# display.net
KiCad netlist of a schematic drawn in Altium Designer
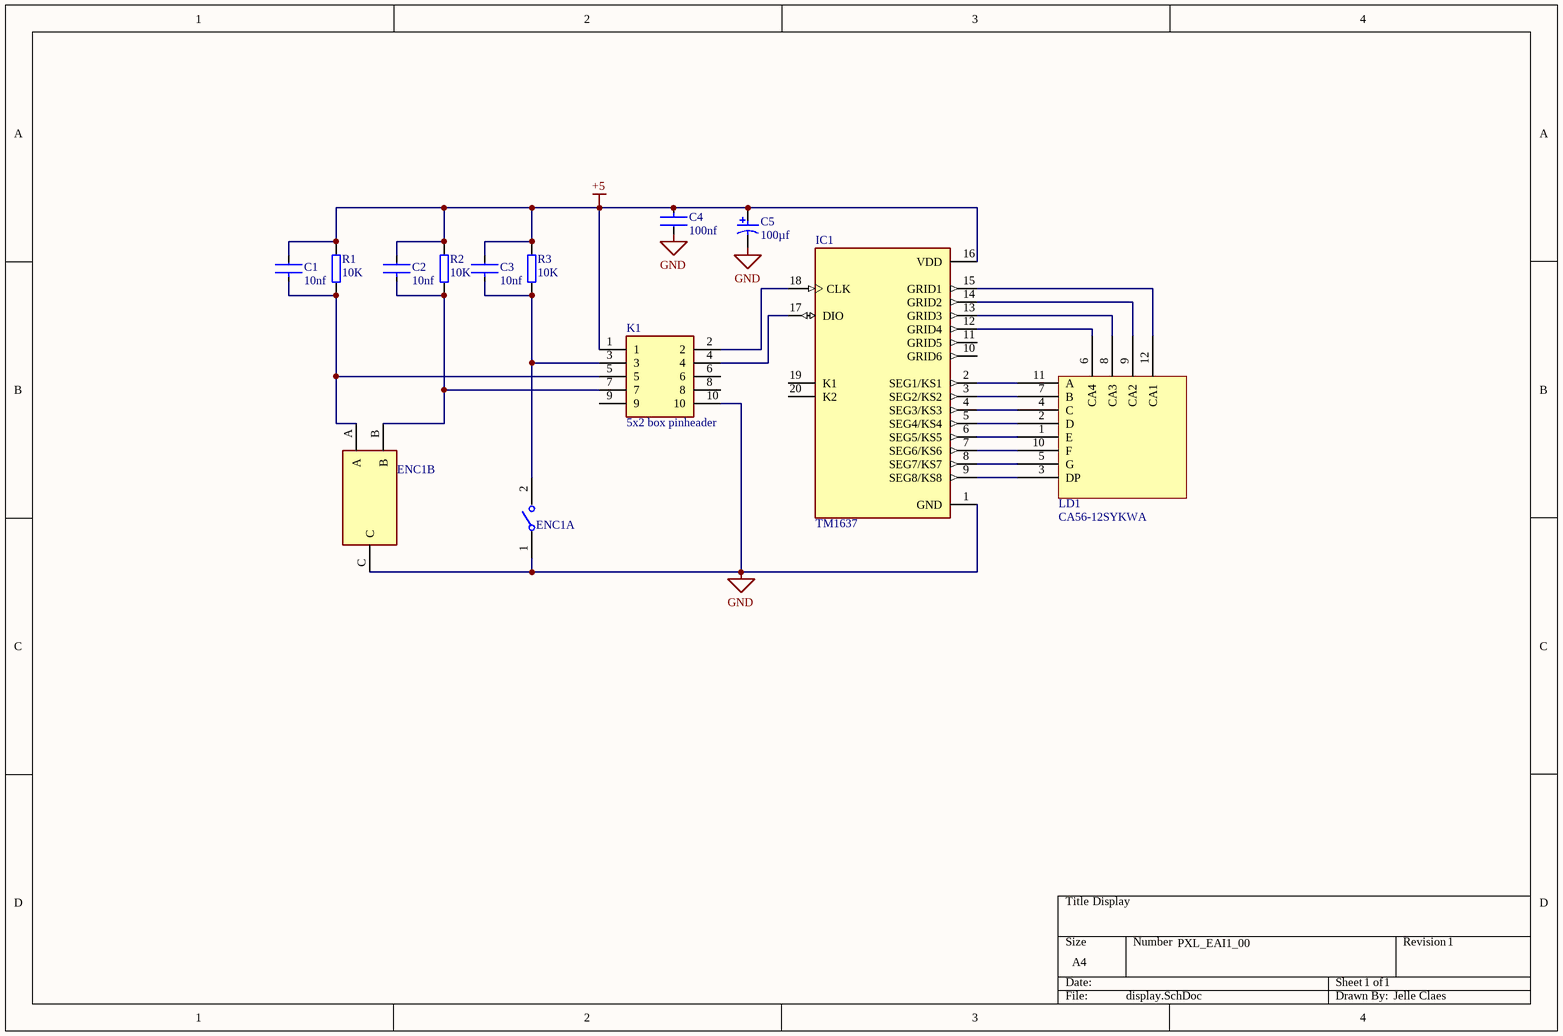
[diagram p0: display.SchDoc]

(export (version "E")
  (design (tool "Eeschema 10.0.6"))
  (components
    (comp (ref "C1")
      (value "10nf")
      (footprint "CC_0805_m")
      (fields
        (field (name "MANUFACTURER") "KEMET")
        (field (name "OCTOPART") "https://octopart.com/c0805c224k5ractu-kemet-144670")
        (field (name "MANUFACTURER PART NUMBER") "C0805C224K5RACTU")
      )
      (libsource (lib "soldeerstation") (part "Capacitor_Ceramic"))
    )
    (comp (ref "C2")
      (value "10nf")
      (footprint "CC_0805_m")
      (fields
        (field (name "MANUFACTURER") "KEMET")
        (field (name "OCTOPART") "https://octopart.com/c0805c224k5ractu-kemet-144670")
        (field (name "MANUFACTURER PART NUMBER") "C0805C224K5RACTU")
      )
      (libsource (lib "soldeerstation") (part "Capacitor_Ceramic"))
    )
    (comp (ref "C3")
      (value "10nf")
      (footprint "CC_0805_m")
      (fields
        (field (name "MANUFACTURER") "KEMET")
        (field (name "OCTOPART") "https://octopart.com/c0805c224k5ractu-kemet-144670")
        (field (name "MANUFACTURER PART NUMBER") "C0805C224K5RACTU")
      )
      (libsource (lib "soldeerstation") (part "Capacitor_Ceramic"))
    )
    (comp (ref "C4")
      (value "100nf")
      (footprint "CC_0805_m")
      (fields
        (field (name "MANUFACTURER") "KEMET")
        (field (name "OCTOPART") "https://octopart.com/c0805c224k5ractu-kemet-144670")
        (field (name "MANUFACTURER PART NUMBER") "C0805C224K5RACTU")
      )
      (libsource (lib "soldeerstation") (part "Capacitor_Ceramic"))
    )
    (comp (ref "C5")
      (value "100µf")
      (footprint "CE_D8_L10")
      (fields (field (name "MANUFACTURER") "Panasonic"))
      (libsource (lib "soldeerstation") (part "Capacitor_Electrolytic"))
    )
    (comp (ref "ENC1")
      (value "PEC11R-4220F-S0012")
      (footprint "PEC11R_4220F_S0012")
      (description "ROTARY ENCODER MECHANICAL 12PPR")
      (libsource (lib "soldeerstation") (part "PEC11R-4220F-S0012"))
    )
    (comp (ref "IC1")
      (value "TM1637")
      (footprint "SOP_20_M")
      (description "LED Drive Control Special Circuit")
      (fields (field (name "MF") "Titan Micro Electronics"))
      (libsource (lib "soldeerstation") (part "TM1637"))
    )
    (comp (ref "K1")
      (value "5x2 box pinheader")
      (footprint "2x5 box pinheader")
      (description "Connector")
      (fields (field (name "MANUFACTURER_PART_NUMBER") "T821110A1S100CEU"))
      (libsource (lib "soldeerstation") (part "5x2 box pinheader"))
    )
    (comp (ref "LD1")
      (value "CA56-12SYKWA")
      (footprint "LCD")
      (libsource (lib "soldeerstation") (part "CA56-12SYKWA"))
    )
    (comp (ref "R1")
      (value "10K")
      (footprint "R_0805_M")
      (fields (field (name "MANUFACTURER") "Vishay Dale") (field (name "PART NUMBER") "CRCW08050000Z0EA"))
      (libsource (lib "soldeerstation") (part "Resistor"))
    )
    (comp (ref "R2")
      (value "10K")
      (footprint "R_0805_M")
      (fields (field (name "MANUFACTURER") "Vishay Dale") (field (name "PART NUMBER") "CRCW08050000Z0EA"))
      (libsource (lib "soldeerstation") (part "Resistor"))
    )
    (comp (ref "R3")
      (value "10K")
      (footprint "R_0805_M")
      (fields (field (name "MANUFACTURER") "Vishay Dale") (field (name "PART NUMBER") "CRCW08050000Z0EA"))
      (libsource (lib "soldeerstation") (part "Resistor"))
    )
  )
  (nets
    (net (code "1") (name "+5") (class "Default")
      (node (ref "C1") (pin "2") (pinfunction "2_2") (pintype "passive"))
      (node (ref "C2") (pin "2") (pinfunction "2_2") (pintype "passive"))
      (node (ref "C3") (pin "2") (pinfunction "2_2") (pintype "passive"))
      (node (ref "C4") (pin "1") (pinfunction "1_1") (pintype "passive"))
      (node (ref "C5") (pin "2") (pinfunction "2_2") (pintype "passive"))
      (node (ref "IC1") (pin "16") (pinfunction "VDD_16") (pintype "power_in"))
      (node (ref "K1") (pin "1") (pinfunction "1_1") (pintype "passive"))
      (node (ref "R1") (pin "2") (pinfunction "2_2") (pintype "passive"))
      (node (ref "R2") (pin "2") (pinfunction "2_2") (pintype "passive"))
      (node (ref "R3") (pin "2") (pinfunction "2_2") (pintype "passive"))
    )
    (net (code "2") (name "GND") (class "Default")
      (node (ref "C4") (pin "2") (pinfunction "2_2") (pintype "passive"))
      (node (ref "C5") (pin "1") (pinfunction "1_1") (pintype "passive"))
      (node (ref "ENC1") (pin "1") (pinfunction "1_1") (pintype "passive"))
      (node (ref "ENC1") (pin "C") (pinfunction "C_C") (pintype "passive"))
      (node (ref "IC1") (pin "1") (pinfunction "GND_1") (pintype "power_in"))
      (node (ref "K1") (pin "10") (pinfunction "10_10") (pintype "passive"))
    )
    (net (code "3") (name "Net-(C1-Pad1)") (class "Default")
      (node (ref "C1") (pin "1") (pinfunction "1_1") (pintype "passive"))
      (node (ref "ENC1") (pin "A") (pinfunction "A_A") (pintype "passive"))
      (node (ref "K1") (pin "5") (pinfunction "5_5") (pintype "passive"))
      (node (ref "R1") (pin "1") (pinfunction "1_1") (pintype "passive"))
    )
    (net (code "4") (name "Net-(C2-Pad1)") (class "Default")
      (node (ref "C2") (pin "1") (pinfunction "1_1") (pintype "passive"))
      (node (ref "ENC1") (pin "B") (pinfunction "B_B") (pintype "passive"))
      (node (ref "K1") (pin "7") (pinfunction "7_7") (pintype "passive"))
      (node (ref "R2") (pin "1") (pinfunction "1_1") (pintype "passive"))
    )
    (net (code "5") (name "Net-(C3-Pad1)") (class "Default")
      (node (ref "C3") (pin "1") (pinfunction "1_1") (pintype "passive"))
      (node (ref "ENC1") (pin "2") (pinfunction "2_2") (pintype "passive"))
      (node (ref "K1") (pin "3") (pinfunction "3_3") (pintype "passive"))
      (node (ref "R3") (pin "1") (pinfunction "1_1") (pintype "passive"))
    )
    (net (code "6") (name "Net-(IC1-CLK)") (class "Default")
      (node (ref "IC1") (pin "18") (pinfunction "CLK_18") (pintype "input"))
      (node (ref "K1") (pin "2") (pinfunction "2_2") (pintype "passive"))
    )
    (net (code "7") (name "Net-(IC1-DIO)") (class "Default")
      (node (ref "IC1") (pin "17") (pinfunction "DIO_17") (pintype "bidirectional"))
      (node (ref "K1") (pin "4") (pinfunction "4_4") (pintype "passive"))
    )
    (net (code "8") (name "Net-(IC1-GRID1)") (class "Default")
      (node (ref "IC1") (pin "15") (pinfunction "GRID1_15") (pintype "output"))
      (node (ref "LD1") (pin "12") (pinfunction "CA1_12") (pintype "passive"))
    )
    (net (code "9") (name "Net-(IC1-GRID2)") (class "Default")
      (node (ref "IC1") (pin "14") (pinfunction "GRID2_14") (pintype "output"))
      (node (ref "LD1") (pin "9") (pinfunction "CA2_9") (pintype "passive"))
    )
    (net (code "10") (name "Net-(IC1-GRID3)") (class "Default")
      (node (ref "IC1") (pin "13") (pinfunction "GRID3_13") (pintype "output"))
      (node (ref "LD1") (pin "8") (pinfunction "CA3_8") (pintype "passive"))
    )
    (net (code "11") (name "Net-(IC1-GRID4)") (class "Default")
      (node (ref "IC1") (pin "12") (pinfunction "GRID4_12") (pintype "output"))
      (node (ref "LD1") (pin "6") (pinfunction "CA4_6") (pintype "passive"))
    )
    (net (code "12") (name "Net-(IC1-SEG1{slash}KS1)") (class "Default")
      (node (ref "IC1") (pin "2") (pinfunction "SEG1/KS1_2") (pintype "output"))
      (node (ref "LD1") (pin "11") (pinfunction "A_11") (pintype "passive"))
    )
    (net (code "13") (name "Net-(IC1-SEG2{slash}KS2)") (class "Default")
      (node (ref "IC1") (pin "3") (pinfunction "SEG2/KS2_3") (pintype "output"))
      (node (ref "LD1") (pin "7") (pinfunction "B_7") (pintype "passive"))
    )
    (net (code "14") (name "Net-(IC1-SEG3{slash}KS3)") (class "Default")
      (node (ref "IC1") (pin "4") (pinfunction "SEG3/KS3_4") (pintype "output"))
      (node (ref "LD1") (pin "4") (pinfunction "C_4") (pintype "passive"))
    )
    (net (code "15") (name "Net-(IC1-SEG4{slash}KS4)") (class "Default")
      (node (ref "IC1") (pin "5") (pinfunction "SEG4/KS4_5") (pintype "output"))
      (node (ref "LD1") (pin "2") (pinfunction "D_2") (pintype "passive"))
    )
    (net (code "16") (name "Net-(IC1-SEG5{slash}KS5)") (class "Default")
      (node (ref "IC1") (pin "6") (pinfunction "SEG5/KS5_6") (pintype "output"))
      (node (ref "LD1") (pin "1") (pinfunction "E_1") (pintype "passive"))
    )
    (net (code "17") (name "Net-(IC1-SEG6{slash}KS6)") (class "Default")
      (node (ref "IC1") (pin "7") (pinfunction "SEG6/KS6_7") (pintype "output"))
      (node (ref "LD1") (pin "10") (pinfunction "F_10") (pintype "passive"))
    )
    (net (code "18") (name "Net-(IC1-SEG7{slash}KS7)") (class "Default")
      (node (ref "IC1") (pin "8") (pinfunction "SEG7/KS7_8") (pintype "output"))
      (node (ref "LD1") (pin "5") (pinfunction "G_5") (pintype "passive"))
    )
    (net (code "19") (name "Net-(IC1-SEG8{slash}KS8)") (class "Default")
      (node (ref "IC1") (pin "9") (pinfunction "SEG8/KS8_9") (pintype "output"))
      (node (ref "LD1") (pin "3") (pinfunction "DP_3") (pintype "passive"))
    )
    (net (code "20") (name "unconnected-(IC1-GRID5-Pad11)") (class "Default")
      (node (ref "IC1") (pin "11") (pinfunction "GRID5_11") (pintype "output"))
    )
    (net (code "21") (name "unconnected-(IC1-GRID6-Pad10)") (class "Default")
      (node (ref "IC1") (pin "10") (pinfunction "GRID6_10") (pintype "output"))
    )
    (net (code "22") (name "unconnected-(IC1-K1-Pad19)") (class "Default")
      (node (ref "IC1") (pin "19") (pinfunction "K1_19") (pintype "passive"))
    )
    (net (code "23") (name "unconnected-(IC1-K2-Pad20)") (class "Default")
      (node (ref "IC1") (pin "20") (pinfunction "K2_20") (pintype "passive"))
    )
    (net (code "24") (name "unconnected-(K1-Pad6)") (class "Default")
      (node (ref "K1") (pin "6") (pinfunction "6_6") (pintype "passive"))
    )
    (net (code "25") (name "unconnected-(K1-Pad8)") (class "Default")
      (node (ref "K1") (pin "8") (pinfunction "8_8") (pintype "passive"))
    )
    (net (code "26") (name "unconnected-(K1-Pad9)") (class "Default")
      (node (ref "K1") (pin "9") (pinfunction "9_9") (pintype "passive"))
    )
  )
)
